# MX8M-Nano-Power.net
KiCad netlist of a schematic drawn in Altium Designer
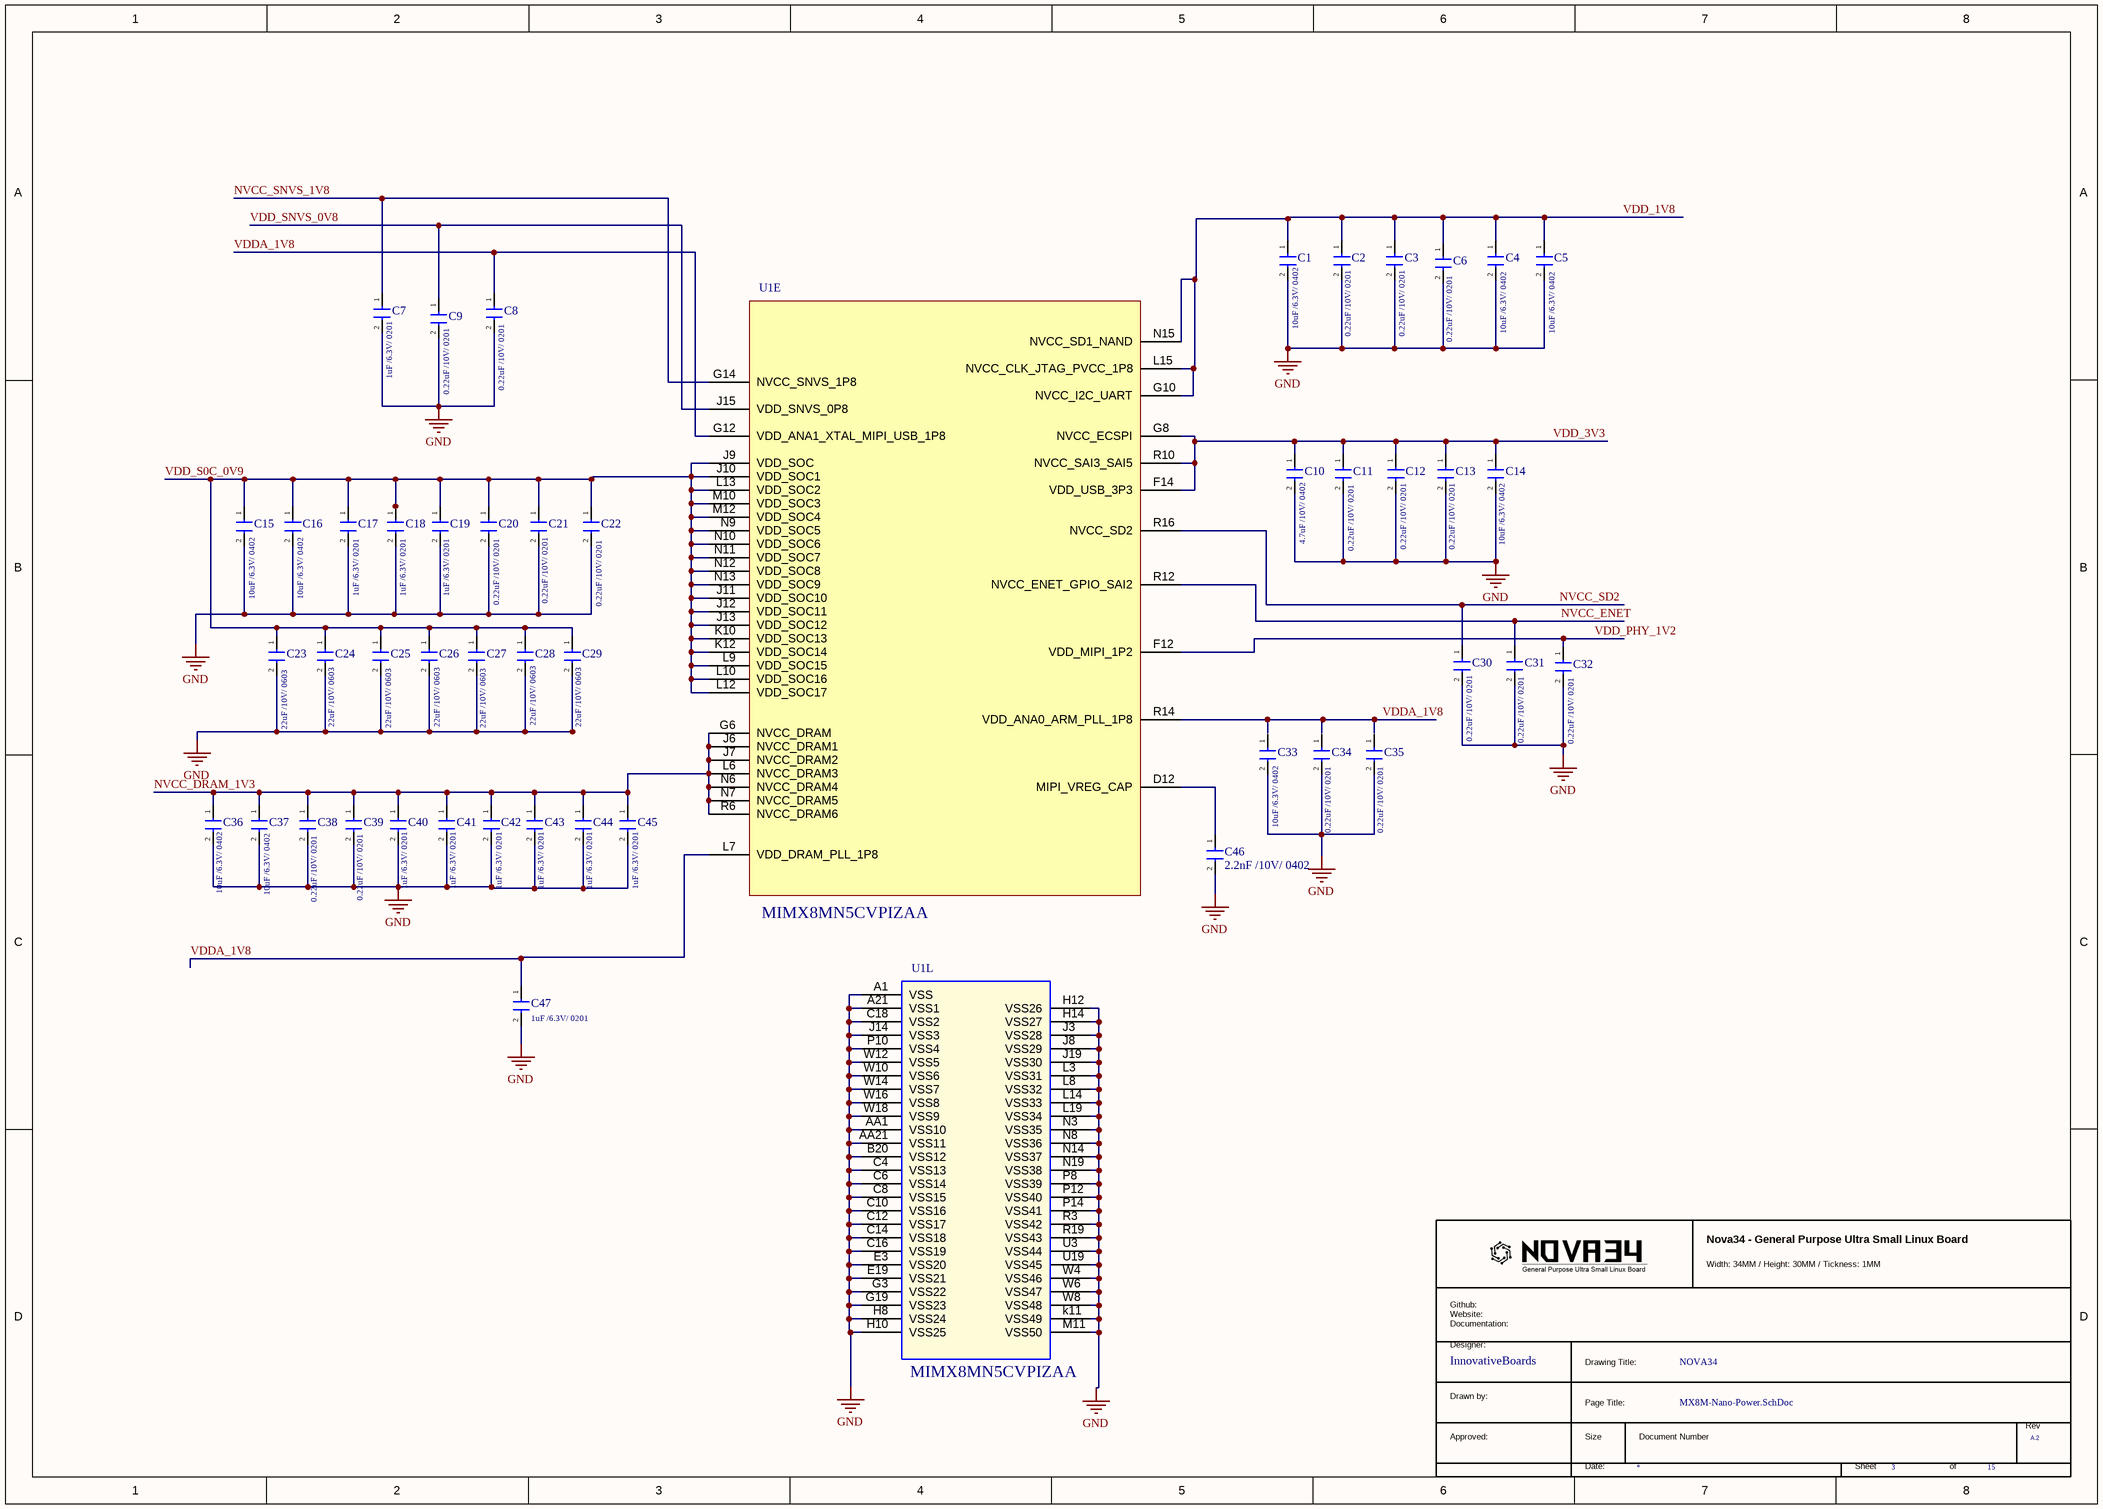
[diagram p0: MX8M-Nano-Power.SchDoc]

(export (version "E")
  (design (tool "Eeschema 10.0.6"))
  (components
    (comp (ref "*")
      (value "TitleBlock_MCPG")
      (fields (field (name "REVCODE") "A.2"))
      (libsource (lib "Nova_SCHLIB") (part "TitleBlock_MCPG"))
    )
    (comp (ref "C1")
      (value "10uF /6.3V/ 0402")
      (footprint "CAPC1005X65N")
      (description "Multilayer Ceramic Capacitors MLCC - SMD/SMT 10 uF 6.3 VDC 20% 0402 X5R")
      (fields
        (field (name "MANUFACTURER_PART_NUMBER") "GRM155R60J106ME15D")
        (field (name "MOUSER PART NUMBER") "81-GRM155R60J106ME5D")
      )
      (libsource (lib "Nova_SCHLIB") (part "GRM155R60J106ME15D"))
    )
    (comp (ref "C2")
      (value "0.22uF /10V/ 0201")
      (footprint "GRM033D70J224ME01D")
      (description "Multilayer Ceramic Capacitors MLCC - SMD/SMT 0201 10VDC 0.22 F 10 X6S")
      (fields
        (field (name "MANUFACTURER_PART_NUMBER") "GRM033C81A224KE01J")
        (field (name "MOUSER PART NUMBER") "81-GRM033C81A224KE1J")
      )
      (libsource (lib "Nova_SCHLIB") (part "GRM033C81A224KE01J"))
    )
    (comp (ref "C3")
      (value "0.22uF /10V/ 0201")
      (footprint "GRM033D70J224ME01D")
      (description "Multilayer Ceramic Capacitors MLCC - SMD/SMT 0201 10VDC 0.22 F 10 X6S")
      (fields
        (field (name "MANUFACTURER_PART_NUMBER") "GRM033C81A224KE01J")
        (field (name "MOUSER PART NUMBER") "81-GRM033C81A224KE1J")
      )
      (libsource (lib "Nova_SCHLIB") (part "GRM033C81A224KE01J"))
    )
    (comp (ref "C4")
      (value "10uF /6.3V/ 0402")
      (footprint "CAPC1005X65N")
      (description "Multilayer Ceramic Capacitors MLCC - SMD/SMT 10 uF 6.3 VDC 20% 0402 X5R")
      (fields
        (field (name "MANUFACTURER_PART_NUMBER") "GRM155R60J106ME15D")
        (field (name "MOUSER PART NUMBER") "81-GRM155R60J106ME5D")
      )
      (libsource (lib "Nova_SCHLIB") (part "GRM155R60J106ME15D"))
    )
    (comp (ref "C5")
      (value "10uF /6.3V/ 0402")
      (footprint "CAPC1005X65N")
      (description "Multilayer Ceramic Capacitors MLCC - SMD/SMT 10 uF 6.3 VDC 20% 0402 X5R")
      (fields
        (field (name "MANUFACTURER_PART_NUMBER") "GRM155R60J106ME15D")
        (field (name "MOUSER PART NUMBER") "81-GRM155R60J106ME5D")
      )
      (libsource (lib "Nova_SCHLIB") (part "GRM155R60J106ME15D"))
    )
    (comp (ref "C6")
      (value "0.22uF /10V/ 0201")
      (footprint "GRM033D70J224ME01D")
      (description "Multilayer Ceramic Capacitors MLCC - SMD/SMT 0201 10VDC 0.22 F 10 X6S")
      (fields
        (field (name "MANUFACTURER_PART_NUMBER") "GRM033C81A224KE01J")
        (field (name "MOUSER PART NUMBER") "81-GRM033C81A224KE1J")
      )
      (libsource (lib "Nova_SCHLIB") (part "GRM033C81A224KE01J"))
    )
    (comp (ref "C7")
      (value "1uF /6.3V/ 0201")
      (footprint "GRM033D70J224ME01D")
      (description "Multilayer Ceramic Capacitors MLCC - SMD/SMT 1 uF 6.3 VDC 20% 0201 X6S")
      (fields
        (field (name "MANUFACTURER_PART_NUMBER") "GRM033C80J105ME05J")
        (field (name "MOUSER PART NUMBER") "81-GRM033C80J105ME5J")
      )
      (libsource (lib "Nova_SCHLIB") (part "GRM033C80J105ME05J"))
    )
    (comp (ref "C8")
      (value "0.22uF /10V/ 0201")
      (footprint "GRM033D70J224ME01D")
      (description "Multilayer Ceramic Capacitors MLCC - SMD/SMT 0201 10VDC 0.22 F 10 X6S")
      (fields
        (field (name "MANUFACTURER_PART_NUMBER") "GRM033C81A224KE01J")
        (field (name "MOUSER PART NUMBER") "81-GRM033C81A224KE1J")
      )
      (libsource (lib "Nova_SCHLIB") (part "GRM033C81A224KE01J"))
    )
    (comp (ref "C9")
      (value "0.22uF /10V/ 0201")
      (footprint "GRM033D70J224ME01D")
      (description "Multilayer Ceramic Capacitors MLCC - SMD/SMT 0201 10VDC 0.22 F 10 X6S")
      (fields
        (field (name "MANUFACTURER_PART_NUMBER") "GRM033C81A224KE01J")
        (field (name "MOUSER PART NUMBER") "81-GRM033C81A224KE1J")
      )
      (libsource (lib "Nova_SCHLIB") (part "GRM033C81A224KE01J"))
    )
    (comp (ref "C10")
      (value "4.7uF /10V/ 0402")
      (footprint "CAPC1005X70N")
      (description "Multilayer Ceramic Capacitors MLCC - SMD/SMT 0402 X6S 4.7 F 20 10VDC AEC-Q200")
      (fields
        (field (name "MANUFACTURER_PART_NUMBER") "GRT155C81A475ME13J")
        (field (name "MOUSER PART NUMBER") "81-GRT155C81A475ME3J")
      )
      (libsource (lib "Nova_SCHLIB") (part "GRT155C81A475ME13J"))
    )
    (comp (ref "C11")
      (value "0.22uF /10V/ 0201")
      (footprint "GRM033D70J224ME01D")
      (description "Multilayer Ceramic Capacitors MLCC - SMD/SMT 0201 10VDC 0.22 F 10 X6S")
      (fields
        (field (name "MANUFACTURER_PART_NUMBER") "GRM033C81A224KE01J")
        (field (name "MOUSER PART NUMBER") "81-GRM033C81A224KE1J")
      )
      (libsource (lib "Nova_SCHLIB") (part "GRM033C81A224KE01J"))
    )
    (comp (ref "C12")
      (value "0.22uF /10V/ 0201")
      (footprint "GRM033D70J224ME01D")
      (description "Multilayer Ceramic Capacitors MLCC - SMD/SMT 0201 10VDC 0.22 F 10 X6S")
      (fields
        (field (name "MANUFACTURER_PART_NUMBER") "GRM033C81A224KE01J")
        (field (name "MOUSER PART NUMBER") "81-GRM033C81A224KE1J")
      )
      (libsource (lib "Nova_SCHLIB") (part "GRM033C81A224KE01J"))
    )
    (comp (ref "C13")
      (value "0.22uF /10V/ 0201")
      (footprint "GRM033D70J224ME01D")
      (description "Multilayer Ceramic Capacitors MLCC - SMD/SMT 0201 10VDC 0.22 F 10 X6S")
      (fields
        (field (name "MANUFACTURER_PART_NUMBER") "GRM033C81A224KE01J")
        (field (name "MOUSER PART NUMBER") "81-GRM033C81A224KE1J")
      )
      (libsource (lib "Nova_SCHLIB") (part "GRM033C81A224KE01J"))
    )
    (comp (ref "C14")
      (value "10uF /6.3V/ 0402")
      (footprint "CAPC1005X65N")
      (description "Multilayer Ceramic Capacitors MLCC - SMD/SMT 10 uF 6.3 VDC 20% 0402 X5R")
      (fields
        (field (name "MANUFACTURER_PART_NUMBER") "GRM155R60J106ME15D")
        (field (name "MOUSER PART NUMBER") "81-GRM155R60J106ME5D")
      )
      (libsource (lib "Nova_SCHLIB") (part "GRM155R60J106ME15D"))
    )
    (comp (ref "C15")
      (value "10uF /6.3V/ 0402")
      (footprint "CAPC1005X65N")
      (description "Multilayer Ceramic Capacitors MLCC - SMD/SMT 10 uF 6.3 VDC 20% 0402 X5R")
      (fields
        (field (name "MANUFACTURER_PART_NUMBER") "GRM155R60J106ME15D")
        (field (name "MOUSER PART NUMBER") "81-GRM155R60J106ME5D")
      )
      (libsource (lib "Nova_SCHLIB") (part "GRM155R60J106ME15D"))
    )
    (comp (ref "C16")
      (value "10uF /6.3V/ 0402")
      (footprint "CAPC1005X65N")
      (description "Multilayer Ceramic Capacitors MLCC - SMD/SMT 10 uF 6.3 VDC 20% 0402 X5R")
      (fields
        (field (name "MANUFACTURER_PART_NUMBER") "GRM155R60J106ME15D")
        (field (name "MOUSER PART NUMBER") "81-GRM155R60J106ME5D")
      )
      (libsource (lib "Nova_SCHLIB") (part "GRM155R60J106ME15D"))
    )
    (comp (ref "C17")
      (value "1uF /6.3V/ 0201")
      (footprint "GRM033D70J224ME01D")
      (description "Multilayer Ceramic Capacitors MLCC - SMD/SMT 1 uF 6.3 VDC 20% 0201 X6S")
      (fields
        (field (name "MANUFACTURER_PART_NUMBER") "GRM033C80J105ME05J")
        (field (name "MOUSER PART NUMBER") "81-GRM033C80J105ME5J")
      )
      (libsource (lib "Nova_SCHLIB") (part "GRM033C80J105ME05J"))
    )
    (comp (ref "C18")
      (value "1uF /6.3V/ 0201")
      (footprint "GRM033D70J224ME01D")
      (description "Multilayer Ceramic Capacitors MLCC - SMD/SMT 1 uF 6.3 VDC 20% 0201 X6S")
      (fields
        (field (name "MANUFACTURER_PART_NUMBER") "GRM033C80J105ME05J")
        (field (name "MOUSER PART NUMBER") "81-GRM033C80J105ME5J")
      )
      (libsource (lib "Nova_SCHLIB") (part "GRM033C80J105ME05J"))
    )
    (comp (ref "C19")
      (value "1uF /6.3V/ 0201")
      (footprint "GRM033D70J224ME01D")
      (description "Multilayer Ceramic Capacitors MLCC - SMD/SMT 1 uF 6.3 VDC 20% 0201 X6S")
      (fields
        (field (name "MANUFACTURER_PART_NUMBER") "GRM033C80J105ME05J")
        (field (name "MOUSER PART NUMBER") "81-GRM033C80J105ME5J")
      )
      (libsource (lib "Nova_SCHLIB") (part "GRM033C80J105ME05J"))
    )
    (comp (ref "C20")
      (value "0.22uF /10V/ 0201")
      (footprint "GRM033D70J224ME01D")
      (description "Multilayer Ceramic Capacitors MLCC - SMD/SMT 0201 10VDC 0.22 F 10 X6S")
      (fields
        (field (name "MANUFACTURER_PART_NUMBER") "GRM033C81A224KE01J")
        (field (name "MOUSER PART NUMBER") "81-GRM033C81A224KE1J")
      )
      (libsource (lib "Nova_SCHLIB") (part "GRM033C81A224KE01J"))
    )
    (comp (ref "C21")
      (value "0.22uF /10V/ 0201")
      (footprint "GRM033D70J224ME01D")
      (description "Multilayer Ceramic Capacitors MLCC - SMD/SMT 0201 10VDC 0.22 F 10 X6S")
      (fields
        (field (name "MANUFACTURER_PART_NUMBER") "GRM033C81A224KE01J")
        (field (name "MOUSER PART NUMBER") "81-GRM033C81A224KE1J")
      )
      (libsource (lib "Nova_SCHLIB") (part "GRM033C81A224KE01J"))
    )
    (comp (ref "C22")
      (value "0.22uF /10V/ 0201")
      (footprint "GRM033D70J224ME01D")
      (description "Multilayer Ceramic Capacitors MLCC - SMD/SMT 0201 10VDC 0.22 F 10 X6S")
      (fields
        (field (name "MANUFACTURER_PART_NUMBER") "GRM033C81A224KE01J")
        (field (name "MOUSER PART NUMBER") "81-GRM033C81A224KE1J")
      )
      (libsource (lib "Nova_SCHLIB") (part "GRM033C81A224KE01J"))
    )
    (comp (ref "C23")
      (value "22uF /10V/ 0603")
      (footprint "GRM18x")
      (description "Multilayer Ceramic Capacitors MLCC - SMD/SMT 22 uF 10 VDC 20% 0603 X5R")
      (fields
        (field (name "MANUFACTURER_PART_NUMBER") "GRM187R61A226ME15D")
        (field (name "MOUSER PART NUMBER") "81-GRM187R61A226ME5D")
      )
      (libsource (lib "Nova_SCHLIB") (part "GRM187R61A226ME15D"))
    )
    (comp (ref "C24")
      (value "22uF /10V/ 0603")
      (footprint "GRM18x")
      (description "Multilayer Ceramic Capacitors MLCC - SMD/SMT 22 uF 10 VDC 20% 0603 X5R")
      (fields
        (field (name "MANUFACTURER_PART_NUMBER") "GRM187R61A226ME15D")
        (field (name "MOUSER PART NUMBER") "81-GRM187R61A226ME5D")
      )
      (libsource (lib "Nova_SCHLIB") (part "GRM187R61A226ME15D"))
    )
    (comp (ref "C25")
      (value "22uF /10V/ 0603")
      (footprint "GRM18x")
      (description "Multilayer Ceramic Capacitors MLCC - SMD/SMT 22 uF 10 VDC 20% 0603 X5R")
      (fields
        (field (name "MANUFACTURER_PART_NUMBER") "GRM187R61A226ME15D")
        (field (name "MOUSER PART NUMBER") "81-GRM187R61A226ME5D")
      )
      (libsource (lib "Nova_SCHLIB") (part "GRM187R61A226ME15D"))
    )
    (comp (ref "C26")
      (value "22uF /10V/ 0603")
      (footprint "GRM18x")
      (description "Multilayer Ceramic Capacitors MLCC - SMD/SMT 22 uF 10 VDC 20% 0603 X5R")
      (fields
        (field (name "MANUFACTURER_PART_NUMBER") "GRM187R61A226ME15D")
        (field (name "MOUSER PART NUMBER") "81-GRM187R61A226ME5D")
      )
      (libsource (lib "Nova_SCHLIB") (part "GRM187R61A226ME15D"))
    )
    (comp (ref "C27")
      (value "22uF /10V/ 0603")
      (footprint "GRM18x")
      (description "Multilayer Ceramic Capacitors MLCC - SMD/SMT 22 uF 10 VDC 20% 0603 X5R")
      (fields
        (field (name "MANUFACTURER_PART_NUMBER") "GRM187R61A226ME15D")
        (field (name "MOUSER PART NUMBER") "81-GRM187R61A226ME5D")
      )
      (libsource (lib "Nova_SCHLIB") (part "GRM187R61A226ME15D"))
    )
    (comp (ref "C28")
      (value "22uF /10V/ 0603")
      (footprint "GRM18x")
      (description "Multilayer Ceramic Capacitors MLCC - SMD/SMT 22 uF 10 VDC 20% 0603 X5R")
      (fields
        (field (name "MANUFACTURER_PART_NUMBER") "GRM187R61A226ME15D")
        (field (name "MOUSER PART NUMBER") "81-GRM187R61A226ME5D")
      )
      (libsource (lib "Nova_SCHLIB") (part "GRM187R61A226ME15D"))
    )
    (comp (ref "C29")
      (value "22uF /10V/ 0603")
      (footprint "GRM18x")
      (description "Multilayer Ceramic Capacitors MLCC - SMD/SMT 22 uF 10 VDC 20% 0603 X5R")
      (fields
        (field (name "MANUFACTURER_PART_NUMBER") "GRM187R61A226ME15D")
        (field (name "MOUSER PART NUMBER") "81-GRM187R61A226ME5D")
      )
      (libsource (lib "Nova_SCHLIB") (part "GRM187R61A226ME15D"))
    )
    (comp (ref "C30")
      (value "0.22uF /10V/ 0201")
      (footprint "GRM033D70J224ME01D")
      (description "Multilayer Ceramic Capacitors MLCC - SMD/SMT 0201 10VDC 0.22 F 10 X6S")
      (fields
        (field (name "MANUFACTURER_PART_NUMBER") "GRM033C81A224KE01J")
        (field (name "MOUSER PART NUMBER") "81-GRM033C81A224KE1J")
      )
      (libsource (lib "Nova_SCHLIB") (part "GRM033C81A224KE01J"))
    )
    (comp (ref "C31")
      (value "0.22uF /10V/ 0201")
      (footprint "GRM033D70J224ME01D")
      (description "Multilayer Ceramic Capacitors MLCC - SMD/SMT 0201 10VDC 0.22 F 10 X6S")
      (fields
        (field (name "MANUFACTURER_PART_NUMBER") "GRM033C81A224KE01J")
        (field (name "MOUSER PART NUMBER") "81-GRM033C81A224KE1J")
      )
      (libsource (lib "Nova_SCHLIB") (part "GRM033C81A224KE01J"))
    )
    (comp (ref "C32")
      (value "0.22uF /10V/ 0201")
      (footprint "GRM033D70J224ME01D")
      (description "Multilayer Ceramic Capacitors MLCC - SMD/SMT 0201 10VDC 0.22 F 10 X6S")
      (fields
        (field (name "MANUFACTURER_PART_NUMBER") "GRM033C81A224KE01J")
        (field (name "MOUSER PART NUMBER") "81-GRM033C81A224KE1J")
      )
      (libsource (lib "Nova_SCHLIB") (part "GRM033C81A224KE01J"))
    )
    (comp (ref "C33")
      (value "10uF /6.3V/ 0402")
      (footprint "CAPC1005X65N")
      (description "Multilayer Ceramic Capacitors MLCC - SMD/SMT 10 uF 6.3 VDC 20% 0402 X5R")
      (fields
        (field (name "MANUFACTURER_PART_NUMBER") "GRM155R60J106ME15D")
        (field (name "MOUSER PART NUMBER") "81-GRM155R60J106ME5D")
      )
      (libsource (lib "Nova_SCHLIB") (part "GRM155R60J106ME15D"))
    )
    (comp (ref "C34")
      (value "0.22uF /10V/ 0201")
      (footprint "GRM033D70J224ME01D")
      (description "Multilayer Ceramic Capacitors MLCC - SMD/SMT 0201 10VDC 0.22 F 10 X6S")
      (fields
        (field (name "MANUFACTURER_PART_NUMBER") "GRM033C81A224KE01J")
        (field (name "MOUSER PART NUMBER") "81-GRM033C81A224KE1J")
      )
      (libsource (lib "Nova_SCHLIB") (part "GRM033C81A224KE01J"))
    )
    (comp (ref "C35")
      (value "0.22uF /10V/ 0201")
      (footprint "GRM033D70J224ME01D")
      (description "Multilayer Ceramic Capacitors MLCC - SMD/SMT 0201 10VDC 0.22 F 10 X6S")
      (fields
        (field (name "MANUFACTURER_PART_NUMBER") "GRM033C81A224KE01J")
        (field (name "MOUSER PART NUMBER") "81-GRM033C81A224KE1J")
      )
      (libsource (lib "Nova_SCHLIB") (part "GRM033C81A224KE01J"))
    )
    (comp (ref "C36")
      (value "10uF /6.3V/ 0402")
      (footprint "CAPC1005X65N")
      (description "Multilayer Ceramic Capacitors MLCC - SMD/SMT 10 uF 6.3 VDC 20% 0402 X5R")
      (fields
        (field (name "MANUFACTURER_PART_NUMBER") "GRM155R60J106ME15D")
        (field (name "MOUSER PART NUMBER") "81-GRM155R60J106ME5D")
      )
      (libsource (lib "Nova_SCHLIB") (part "GRM155R60J106ME15D"))
    )
    (comp (ref "C37")
      (value "10uF /6.3V/ 0402")
      (footprint "CAPC1005X65N")
      (description "Multilayer Ceramic Capacitors MLCC - SMD/SMT 10 uF 6.3 VDC 20% 0402 X5R")
      (fields
        (field (name "MANUFACTURER_PART_NUMBER") "GRM155R60J106ME15D")
        (field (name "MOUSER PART NUMBER") "81-GRM155R60J106ME5D")
      )
      (libsource (lib "Nova_SCHLIB") (part "GRM155R60J106ME15D"))
    )
    (comp (ref "C38")
      (value "0.22uF /10V/ 0201")
      (footprint "GRM033D70J224ME01D")
      (description "Multilayer Ceramic Capacitors MLCC - SMD/SMT 0201 10VDC 0.22 F 10 X6S")
      (fields
        (field (name "MANUFACTURER_PART_NUMBER") "GRM033C81A224KE01J")
        (field (name "MOUSER PART NUMBER") "81-GRM033C81A224KE1J")
      )
      (libsource (lib "Nova_SCHLIB") (part "GRM033C81A224KE01J"))
    )
    (comp (ref "C39")
      (value "0.22uF /10V/ 0201")
      (footprint "GRM033D70J224ME01D")
      (description "Multilayer Ceramic Capacitors MLCC - SMD/SMT 0201 10VDC 0.22 F 10 X6S")
      (fields
        (field (name "MANUFACTURER_PART_NUMBER") "GRM033C81A224KE01J")
        (field (name "MOUSER PART NUMBER") "81-GRM033C81A224KE1J")
      )
      (libsource (lib "Nova_SCHLIB") (part "GRM033C81A224KE01J"))
    )
    (comp (ref "C40")
      (value "1uF /6.3V/ 0201")
      (footprint "GRM033D70J224ME01D")
      (description "Multilayer Ceramic Capacitors MLCC - SMD/SMT 1 uF 6.3 VDC 20% 0201 X6S")
      (fields
        (field (name "MANUFACTURER_PART_NUMBER") "GRM033C80J105ME05J")
        (field (name "MOUSER PART NUMBER") "81-GRM033C80J105ME5J")
      )
      (libsource (lib "Nova_SCHLIB") (part "GRM033C80J105ME05J"))
    )
    (comp (ref "C41")
      (value "1uF /6.3V/ 0201")
      (footprint "GRM033D70J224ME01D")
      (description "Multilayer Ceramic Capacitors MLCC - SMD/SMT 1 uF 6.3 VDC 20% 0201 X6S")
      (fields
        (field (name "MANUFACTURER_PART_NUMBER") "GRM033C80J105ME05J")
        (field (name "MOUSER PART NUMBER") "81-GRM033C80J105ME5J")
      )
      (libsource (lib "Nova_SCHLIB") (part "GRM033C80J105ME05J"))
    )
    (comp (ref "C42")
      (value "1uF /6.3V/ 0201")
      (footprint "GRM033D70J224ME01D")
      (description "Multilayer Ceramic Capacitors MLCC - SMD/SMT 1 uF 6.3 VDC 20% 0201 X6S")
      (fields
        (field (name "MANUFACTURER_PART_NUMBER") "GRM033C80J105ME05J")
        (field (name "MOUSER PART NUMBER") "81-GRM033C80J105ME5J")
      )
      (libsource (lib "Nova_SCHLIB") (part "GRM033C80J105ME05J"))
    )
    (comp (ref "C43")
      (value "1uF /6.3V/ 0201")
      (footprint "GRM033D70J224ME01D")
      (description "Multilayer Ceramic Capacitors MLCC - SMD/SMT 1 uF 6.3 VDC 20% 0201 X6S")
      (fields
        (field (name "MANUFACTURER_PART_NUMBER") "GRM033C80J105ME05J")
        (field (name "MOUSER PART NUMBER") "81-GRM033C80J105ME5J")
      )
      (libsource (lib "Nova_SCHLIB") (part "GRM033C80J105ME05J"))
    )
    (comp (ref "C44")
      (value "1uF /6.3V/ 0201")
      (footprint "GRM033D70J224ME01D")
      (description "Multilayer Ceramic Capacitors MLCC - SMD/SMT 1 uF 6.3 VDC 20% 0201 X6S")
      (fields
        (field (name "MANUFACTURER_PART_NUMBER") "GRM033C80J105ME05J")
        (field (name "MOUSER PART NUMBER") "81-GRM033C80J105ME5J")
      )
      (libsource (lib "Nova_SCHLIB") (part "GRM033C80J105ME05J"))
    )
    (comp (ref "C45")
      (value "1uF /6.3V/ 0201")
      (footprint "GRM033D70J224ME01D")
      (description "Multilayer Ceramic Capacitors MLCC - SMD/SMT 1 uF 6.3 VDC 20% 0201 X6S")
      (fields
        (field (name "MANUFACTURER_PART_NUMBER") "GRM033C80J105ME05J")
        (field (name "MOUSER PART NUMBER") "81-GRM033C80J105ME5J")
      )
      (libsource (lib "Nova_SCHLIB") (part "GRM033C80J105ME05J"))
    )
    (comp (ref "C46")
      (value "2.2nF /10V/ 0402")
      (footprint "CAPC1005X70N")
      (description "Multilayer Ceramic Capacitors MLCC - SMD/SMT 2200 pF 10 VDC 10% 0402 X5R")
      (fields
        (field (name "MANUFACTURER_PART_NUMBER") "GRM155R61A222KA01D")
        (field (name "MOUSER PART NUMBER") "81-GRM155R61A222KA1D")
      )
      (libsource (lib "Nova_SCHLIB") (part "GRM155R61A222KA01D"))
    )
    (comp (ref "C47")
      (value "1uF /6.3V/ 0201")
      (footprint "GRM033D70J224ME01D")
      (description "Multilayer Ceramic Capacitors MLCC - SMD/SMT 1 uF 6.3 VDC 20% 0201 X6S")
      (fields
        (field (name "MANUFACTURER_PART_NUMBER") "GRM033C80J105ME05J")
        (field (name "MOUSER PART NUMBER") "81-GRM033C80J105ME5J")
      )
      (libsource (lib "Nova_SCHLIB") (part "GRM033C80J105ME05J"))
    )
    (comp (ref "U1")
      (value "MIMX8MN5CVPIZAA")
      (footprint "BGA306C50P21X21_1100X1100X101")
      (description "IC CPU QUAD CORTEX A53+M7 1.4GHZ -- BGA306")
      (libsource (lib "Nova_SCHLIB") (part "MIMX8MN"))
    )
  )
  (nets
    (net (code "1") (name "/NVCC_DRAM_1V3") (class "Default")
      (node (ref "C36") (pin "1") (pinfunction "1_1") (pintype "passive"))
      (node (ref "C37") (pin "1") (pinfunction "1_1") (pintype "passive"))
      (node (ref "C38") (pin "1") (pinfunction "1_1") (pintype "passive"))
      (node (ref "C39") (pin "1") (pinfunction "1_1") (pintype "passive"))
      (node (ref "C40") (pin "1") (pinfunction "1_1") (pintype "passive"))
      (node (ref "C41") (pin "1") (pinfunction "1_1") (pintype "passive"))
      (node (ref "C42") (pin "1") (pinfunction "1_1") (pintype "passive"))
      (node (ref "C43") (pin "1") (pinfunction "1_1") (pintype "passive"))
      (node (ref "C44") (pin "1") (pinfunction "1_1") (pintype "passive"))
      (node (ref "C45") (pin "1") (pinfunction "1_1") (pintype "passive"))
      (node (ref "U1") (pin "G6") (pinfunction "NVCC_DRAM_G6") (pintype "passive"))
      (node (ref "U1") (pin "J6") (pinfunction "NVCC_DRAM1_J6") (pintype "passive"))
      (node (ref "U1") (pin "J7") (pinfunction "NVCC_DRAM2_J7") (pintype "passive"))
      (node (ref "U1") (pin "L6") (pinfunction "NVCC_DRAM3_L6") (pintype "passive"))
      (node (ref "U1") (pin "N6") (pinfunction "NVCC_DRAM4_N6") (pintype "passive"))
      (node (ref "U1") (pin "N7") (pinfunction "NVCC_DRAM5_N7") (pintype "passive"))
      (node (ref "U1") (pin "R6") (pinfunction "NVCC_DRAM6_R6") (pintype "passive"))
    )
    (net (code "2") (name "/NVCC_ENET") (class "Default")
      (node (ref "C31") (pin "1") (pinfunction "1_1") (pintype "passive"))
      (node (ref "U1") (pin "R12") (pinfunction "NVCC_ENET_GPIO_SAI2_R12") (pintype "passive"))
    )
    (net (code "3") (name "/NVCC_SD2") (class "Default")
      (node (ref "C30") (pin "1") (pinfunction "1_1") (pintype "passive"))
      (node (ref "U1") (pin "R16") (pinfunction "NVCC_SD2_R16") (pintype "passive"))
    )
    (net (code "4") (name "/NVCC_SNVS_1V8") (class "Default")
      (node (ref "C7") (pin "1") (pinfunction "1_1") (pintype "passive"))
      (node (ref "U1") (pin "G14") (pinfunction "NVCC_SNVS_1P8_G14") (pintype "passive"))
    )
    (net (code "5") (name "/VDDA_1V8") (class "Default")
      (node (ref "C47") (pin "1") (pinfunction "1_1") (pintype "passive"))
      (node (ref "C8") (pin "1") (pinfunction "1_1") (pintype "passive"))
      (node (ref "U1") (pin "G12") (pinfunction "VDD_ANA1_XTAL_MIPI_USB_1P8_G12") (pintype "passive"))
      (node (ref "U1") (pin "L7") (pinfunction "VDD_DRAM_PLL_1P8_L7") (pintype "passive"))
      (node (ref "U1") (pin "R14") (pinfunction "VDD_ANA0_ARM_PLL_1P8_R14") (pintype "passive"))
    )
    (net (code "6") (name "/VDD_1V8") (class "Default")
      (node (ref "C1") (pin "1") (pinfunction "1_1") (pintype "passive"))
      (node (ref "C2") (pin "1") (pinfunction "1_1") (pintype "passive"))
      (node (ref "C3") (pin "1") (pinfunction "1_1") (pintype "passive"))
      (node (ref "C4") (pin "1") (pinfunction "1_1") (pintype "passive"))
      (node (ref "C5") (pin "1") (pinfunction "1_1") (pintype "passive"))
      (node (ref "C6") (pin "1") (pinfunction "1_1") (pintype "passive"))
      (node (ref "U1") (pin "G10") (pinfunction "NVCC_I2C_UART_G10") (pintype "passive"))
      (node (ref "U1") (pin "L15") (pinfunction "NVCC_CLK_JTAG_PVCC_1P8_L15") (pintype "passive"))
      (node (ref "U1") (pin "N15") (pinfunction "NVCC_SD1_NAND_N15") (pintype "passive"))
    )
    (net (code "7") (name "/VDD_3V3") (class "Default")
      (node (ref "C10") (pin "1") (pinfunction "1_1") (pintype "passive"))
      (node (ref "C11") (pin "1") (pinfunction "1_1") (pintype "passive"))
      (node (ref "C12") (pin "1") (pinfunction "1_1") (pintype "passive"))
      (node (ref "C13") (pin "1") (pinfunction "1_1") (pintype "passive"))
      (node (ref "C14") (pin "1") (pinfunction "1_1") (pintype "passive"))
      (node (ref "U1") (pin "F14") (pinfunction "VDD_USB_3P3_F14") (pintype "passive"))
      (node (ref "U1") (pin "G8") (pinfunction "NVCC_ECSPI_G8") (pintype "passive"))
      (node (ref "U1") (pin "R10") (pinfunction "NVCC_SAI3_SAI5_R10") (pintype "passive"))
    )
    (net (code "8") (name "/VDD_PHY_1V2") (class "Default")
      (node (ref "C32") (pin "1") (pinfunction "1_1") (pintype "passive"))
      (node (ref "U1") (pin "F12") (pinfunction "VDD_MIPI_1P2_F12") (pintype "passive"))
    )
    (net (code "9") (name "/VDD_S0C_0V9") (class "Default")
      (node (ref "C15") (pin "1") (pinfunction "1_1") (pintype "passive"))
      (node (ref "C16") (pin "1") (pinfunction "1_1") (pintype "passive"))
      (node (ref "C17") (pin "1") (pinfunction "1_1") (pintype "passive"))
      (node (ref "C18") (pin "1") (pinfunction "1_1") (pintype "passive"))
      (node (ref "C19") (pin "1") (pinfunction "1_1") (pintype "passive"))
      (node (ref "C20") (pin "1") (pinfunction "1_1") (pintype "passive"))
      (node (ref "C21") (pin "1") (pinfunction "1_1") (pintype "passive"))
      (node (ref "C22") (pin "1") (pinfunction "1_1") (pintype "passive"))
      (node (ref "C23") (pin "1") (pinfunction "1_1") (pintype "passive"))
      (node (ref "C24") (pin "1") (pinfunction "1_1") (pintype "passive"))
      (node (ref "C25") (pin "1") (pinfunction "1_1") (pintype "passive"))
      (node (ref "C26") (pin "1") (pinfunction "1_1") (pintype "passive"))
      (node (ref "C27") (pin "1") (pinfunction "1_1") (pintype "passive"))
      (node (ref "C28") (pin "1") (pinfunction "1_1") (pintype "passive"))
      (node (ref "C29") (pin "1") (pinfunction "1_1") (pintype "passive"))
      (node (ref "U1") (pin "J10") (pinfunction "VDD_SOC1_J10") (pintype "passive"))
      (node (ref "U1") (pin "J11") (pinfunction "VDD_SOC10_J11") (pintype "passive"))
      (node (ref "U1") (pin "J12") (pinfunction "VDD_SOC11_J12") (pintype "passive"))
      (node (ref "U1") (pin "J13") (pinfunction "VDD_SOC12_J13") (pintype "passive"))
      (node (ref "U1") (pin "J9") (pinfunction "VDD_SOC_J9") (pintype "passive"))
      (node (ref "U1") (pin "K10") (pinfunction "VDD_SOC13_K10") (pintype "passive"))
      (node (ref "U1") (pin "K12") (pinfunction "VDD_SOC14_K12") (pintype "passive"))
      (node (ref "U1") (pin "L10") (pinfunction "VDD_SOC16_L10") (pintype "passive"))
      (node (ref "U1") (pin "L12") (pinfunction "VDD_SOC17_L12") (pintype "passive"))
      (node (ref "U1") (pin "L13") (pinfunction "VDD_SOC2_L13") (pintype "passive"))
      (node (ref "U1") (pin "L9") (pinfunction "VDD_SOC15_L9") (pintype "passive"))
      (node (ref "U1") (pin "M10") (pinfunction "VDD_SOC3_M10") (pintype "passive"))
      (node (ref "U1") (pin "M12") (pinfunction "VDD_SOC4_M12") (pintype "passive"))
      (node (ref "U1") (pin "N10") (pinfunction "VDD_SOC6_N10") (pintype "passive"))
      (node (ref "U1") (pin "N11") (pinfunction "VDD_SOC7_N11") (pintype "passive"))
      (node (ref "U1") (pin "N12") (pinfunction "VDD_SOC8_N12") (pintype "passive"))
      (node (ref "U1") (pin "N13") (pinfunction "VDD_SOC9_N13") (pintype "passive"))
      (node (ref "U1") (pin "N9") (pinfunction "VDD_SOC5_N9") (pintype "passive"))
    )
    (net (code "10") (name "/VDD_SNVS_0V8") (class "Default")
      (node (ref "C9") (pin "1") (pinfunction "1_1") (pintype "passive"))
      (node (ref "U1") (pin "J15") (pinfunction "VDD_SNVS_0P8_J15") (pintype "passive"))
    )
    (net (code "11") (name "GND") (class "Default")
      (node (ref "C1") (pin "2") (pinfunction "2_2") (pintype "passive"))
      (node (ref "C10") (pin "2") (pinfunction "2_2") (pintype "passive"))
      (node (ref "C11") (pin "2") (pinfunction "2_2") (pintype "passive"))
      (node (ref "C12") (pin "2") (pinfunction "2_2") (pintype "passive"))
      (node (ref "C13") (pin "2") (pinfunction "2_2") (pintype "passive"))
      (node (ref "C14") (pin "2") (pinfunction "2_2") (pintype "passive"))
      (node (ref "C15") (pin "2") (pinfunction "2_2") (pintype "passive"))
      (node (ref "C16") (pin "2") (pinfunction "2_2") (pintype "passive"))
      (node (ref "C17") (pin "2") (pinfunction "2_2") (pintype "passive"))
      (node (ref "C18") (pin "2") (pinfunction "2_2") (pintype "passive"))
      (node (ref "C19") (pin "2") (pinfunction "2_2") (pintype "passive"))
      (node (ref "C2") (pin "2") (pinfunction "2_2") (pintype "passive"))
      (node (ref "C20") (pin "2") (pinfunction "2_2") (pintype "passive"))
      (node (ref "C21") (pin "2") (pinfunction "2_2") (pintype "passive"))
      (node (ref "C22") (pin "2") (pinfunction "2_2") (pintype "passive"))
      (node (ref "C23") (pin "2") (pinfunction "2_2") (pintype "passive"))
      (node (ref "C24") (pin "2") (pinfunction "2_2") (pintype "passive"))
      (node (ref "C25") (pin "2") (pinfunction "2_2") (pintype "passive"))
      (node (ref "C26") (pin "2") (pinfunction "2_2") (pintype "passive"))
      (node (ref "C27") (pin "2") (pinfunction "2_2") (pintype "passive"))
      (node (ref "C28") (pin "2") (pinfunction "2_2") (pintype "passive"))
      (node (ref "C29") (pin "2") (pinfunction "2_2") (pintype "passive"))
      (node (ref "C3") (pin "2") (pinfunction "2_2") (pintype "passive"))
      (node (ref "C30") (pin "2") (pinfunction "2_2") (pintype "passive"))
      (node (ref "C31") (pin "2") (pinfunction "2_2") (pintype "passive"))
      (node (ref "C32") (pin "2") (pinfunction "2_2") (pintype "passive"))
      (node (ref "C33") (pin "2") (pinfunction "2_2") (pintype "passive"))
      (node (ref "C34") (pin "2") (pinfunction "2_2") (pintype "passive"))
      (node (ref "C35") (pin "2") (pinfunction "2_2") (pintype "passive"))
      (node (ref "C36") (pin "2") (pinfunction "2_2") (pintype "passive"))
      (node (ref "C37") (pin "2") (pinfunction "2_2") (pintype "passive"))
      (node (ref "C38") (pin "2") (pinfunction "2_2") (pintype "passive"))
      (node (ref "C39") (pin "2") (pinfunction "2_2") (pintype "passive"))
      (node (ref "C4") (pin "2") (pinfunction "2_2") (pintype "passive"))
      (node (ref "C40") (pin "2") (pinfunction "2_2") (pintype "passive"))
      (node (ref "C41") (pin "2") (pinfunction "2_2") (pintype "passive"))
      (node (ref "C42") (pin "2") (pinfunction "2_2") (pintype "passive"))
      (node (ref "C43") (pin "2") (pinfunction "2_2") (pintype "passive"))
      (node (ref "C44") (pin "2") (pinfunction "2_2") (pintype "passive"))
      (node (ref "C45") (pin "2") (pinfunction "2_2") (pintype "passive"))
      (node (ref "C46") (pin "2") (pinfunction "2_2") (pintype "passive"))
      (node (ref "C47") (pin "2") (pinfunction "2_2") (pintype "passive"))
      (node (ref "C5") (pin "2") (pinfunction "2_2") (pintype "passive"))
      (node (ref "C6") (pin "2") (pinfunction "2_2") (pintype "passive"))
      (node (ref "C7") (pin "2") (pinfunction "2_2") (pintype "passive"))
      (node (ref "C8") (pin "2") (pinfunction "2_2") (pintype "passive"))
      (node (ref "C9") (pin "2") (pinfunction "2_2") (pintype "passive"))
      (node (ref "U1") (pin "A1") (pinfunction "VSS_A1") (pintype "passive"))
      (node (ref "U1") (pin "A21") (pinfunction "VSS1_A21") (pintype "passive"))
      (node (ref "U1") (pin "AA1") (pinfunction "VSS10_AA1") (pintype "passive"))
      (node (ref "U1") (pin "AA21") (pinfunction "VSS11_AA21") (pintype "passive"))
      (node (ref "U1") (pin "B20") (pinfunction "VSS12_B20") (pintype "passive"))
      (node (ref "U1") (pin "C10") (pinfunction "VSS16_C10") (pintype "passive"))
      (node (ref "U1") (pin "C12") (pinfunction "VSS17_C12") (pintype "passive"))
      (node (ref "U1") (pin "C14") (pinfunction "VSS18_C14") (pintype "passive"))
      (node (ref "U1") (pin "C16") (pinfunction "VSS19_C16") (pintype "passive"))
      (node (ref "U1") (pin "C18") (pinfunction "VSS2_C18") (pintype "passive"))
      (node (ref "U1") (pin "C4") (pinfunction "VSS13_C4") (pintype "passive"))
      (node (ref "U1") (pin "C6") (pinfunction "VSS14_C6") (pintype "passive"))
      (node (ref "U1") (pin "C8") (pinfunction "VSS15_C8") (pintype "passive"))
      (node (ref "U1") (pin "E19") (pinfunction "VSS21_E19") (pintype "passive"))
      (node (ref "U1") (pin "E3") (pinfunction "VSS20_E3") (pintype "passive"))
      (node (ref "U1") (pin "G19") (pinfunction "VSS23_G19") (pintype "passive"))
      (node (ref "U1") (pin "G3") (pinfunction "VSS22_G3") (pintype "passive"))
      (node (ref "U1") (pin "H10") (pinfunction "VSS25_H10") (pintype "passive"))
      (node (ref "U1") (pin "H12") (pinfunction "VSS26_H12") (pintype "passive"))
      (node (ref "U1") (pin "H14") (pinfunction "VSS27_H14") (pintype "passive"))
      (node (ref "U1") (pin "H8") (pinfunction "VSS24_H8") (pintype "passive"))
      (node (ref "U1") (pin "J14") (pinfunction "VSS3_J14") (pintype "passive"))
      (node (ref "U1") (pin "J19") (pinfunction "VSS30_J19") (pintype "passive"))
      (node (ref "U1") (pin "J3") (pinfunction "VSS28_J3") (pintype "passive"))
      (node (ref "U1") (pin "J8") (pinfunction "VSS29_J8") (pintype "passive"))
      (node (ref "U1") (pin "L14") (pinfunction "VSS33_L14") (pintype "passive"))
      (node (ref "U1") (pin "L19") (pinfunction "VSS34_L19") (pintype "passive"))
      (node (ref "U1") (pin "L3") (pinfunction "VSS31_L3") (pintype "passive"))
      (node (ref "U1") (pin "L8") (pinfunction "VSS32_L8") (pintype "passive"))
      (node (ref "U1") (pin "M11") (pinfunction "VSS50_M11") (pintype "passive"))
      (node (ref "U1") (pin "N14") (pinfunction "VSS37_N14") (pintype "passive"))
      (node (ref "U1") (pin "N19") (pinfunction "VSS38_N19") (pintype "passive"))
      (node (ref "U1") (pin "N3") (pinfunction "VSS35_N3") (pintype "passive"))
      (node (ref "U1") (pin "N8") (pinfunction "VSS36_N8") (pintype "passive"))
      (node (ref "U1") (pin "P10") (pinfunction "VSS4_P10") (pintype "passive"))
      (node (ref "U1") (pin "P12") (pinfunction "VSS40_P12") (pintype "passive"))
      (node (ref "U1") (pin "P14") (pinfunction "VSS41_P14") (pintype "passive"))
      (node (ref "U1") (pin "P8") (pinfunction "VSS39_P8") (pintype "passive"))
      (node (ref "U1") (pin "R19") (pinfunction "VSS43_R19") (pintype "passive"))
      (node (ref "U1") (pin "R3") (pinfunction "VSS42_R3") (pintype "passive"))
      (node (ref "U1") (pin "U19") (pinfunction "VSS45_U19") (pintype "passive"))
      (node (ref "U1") (pin "U3") (pinfunction "VSS44_U3") (pintype "passive"))
      (node (ref "U1") (pin "W10") (pinfunction "VSS6_W10") (pintype "passive"))
      (node (ref "U1") (pin "W12") (pinfunction "VSS5_W12") (pintype "passive"))
      (node (ref "U1") (pin "W14") (pinfunction "VSS7_W14") (pintype "passive"))
      (node (ref "U1") (pin "W16") (pinfunction "VSS8_W16") (pintype "passive"))
      (node (ref "U1") (pin "W18") (pinfunction "VSS9_W18") (pintype "passive"))
      (node (ref "U1") (pin "W4") (pinfunction "VSS46_W4") (pintype "passive"))
      (node (ref "U1") (pin "W6") (pinfunction "VSS47_W6") (pintype "passive"))
      (node (ref "U1") (pin "W8") (pinfunction "VSS48_W8") (pintype "passive"))
      (node (ref "U1") (pin "k11") (pinfunction "VSS49_k11") (pintype "passive"))
    )
    (net (code "12") (name "Net-(U1E-MIPI_VREG_CAP)") (class "Default")
      (node (ref "C46") (pin "1") (pinfunction "1_1") (pintype "passive"))
      (node (ref "U1") (pin "D12") (pinfunction "MIPI_VREG_CAP_D12") (pintype "passive"))
    )
    (net (code "13") (name "unconnected-(C33-Pad1)") (class "Default")
      (node (ref "C33") (pin "1") (pinfunction "1_1") (pintype "passive"))
    )
    (net (code "14") (name "unconnected-(C34-Pad1)") (class "Default")
      (node (ref "C34") (pin "1") (pinfunction "1_1") (pintype "passive"))
    )
    (net (code "15") (name "unconnected-(C35-Pad1)") (class "Default")
      (node (ref "C35") (pin "1") (pinfunction "1_1") (pintype "passive"))
    )
  )
)
